# Sheet_MCU_IO.net
KiCad netlist of a schematic drawn in Altium Designer
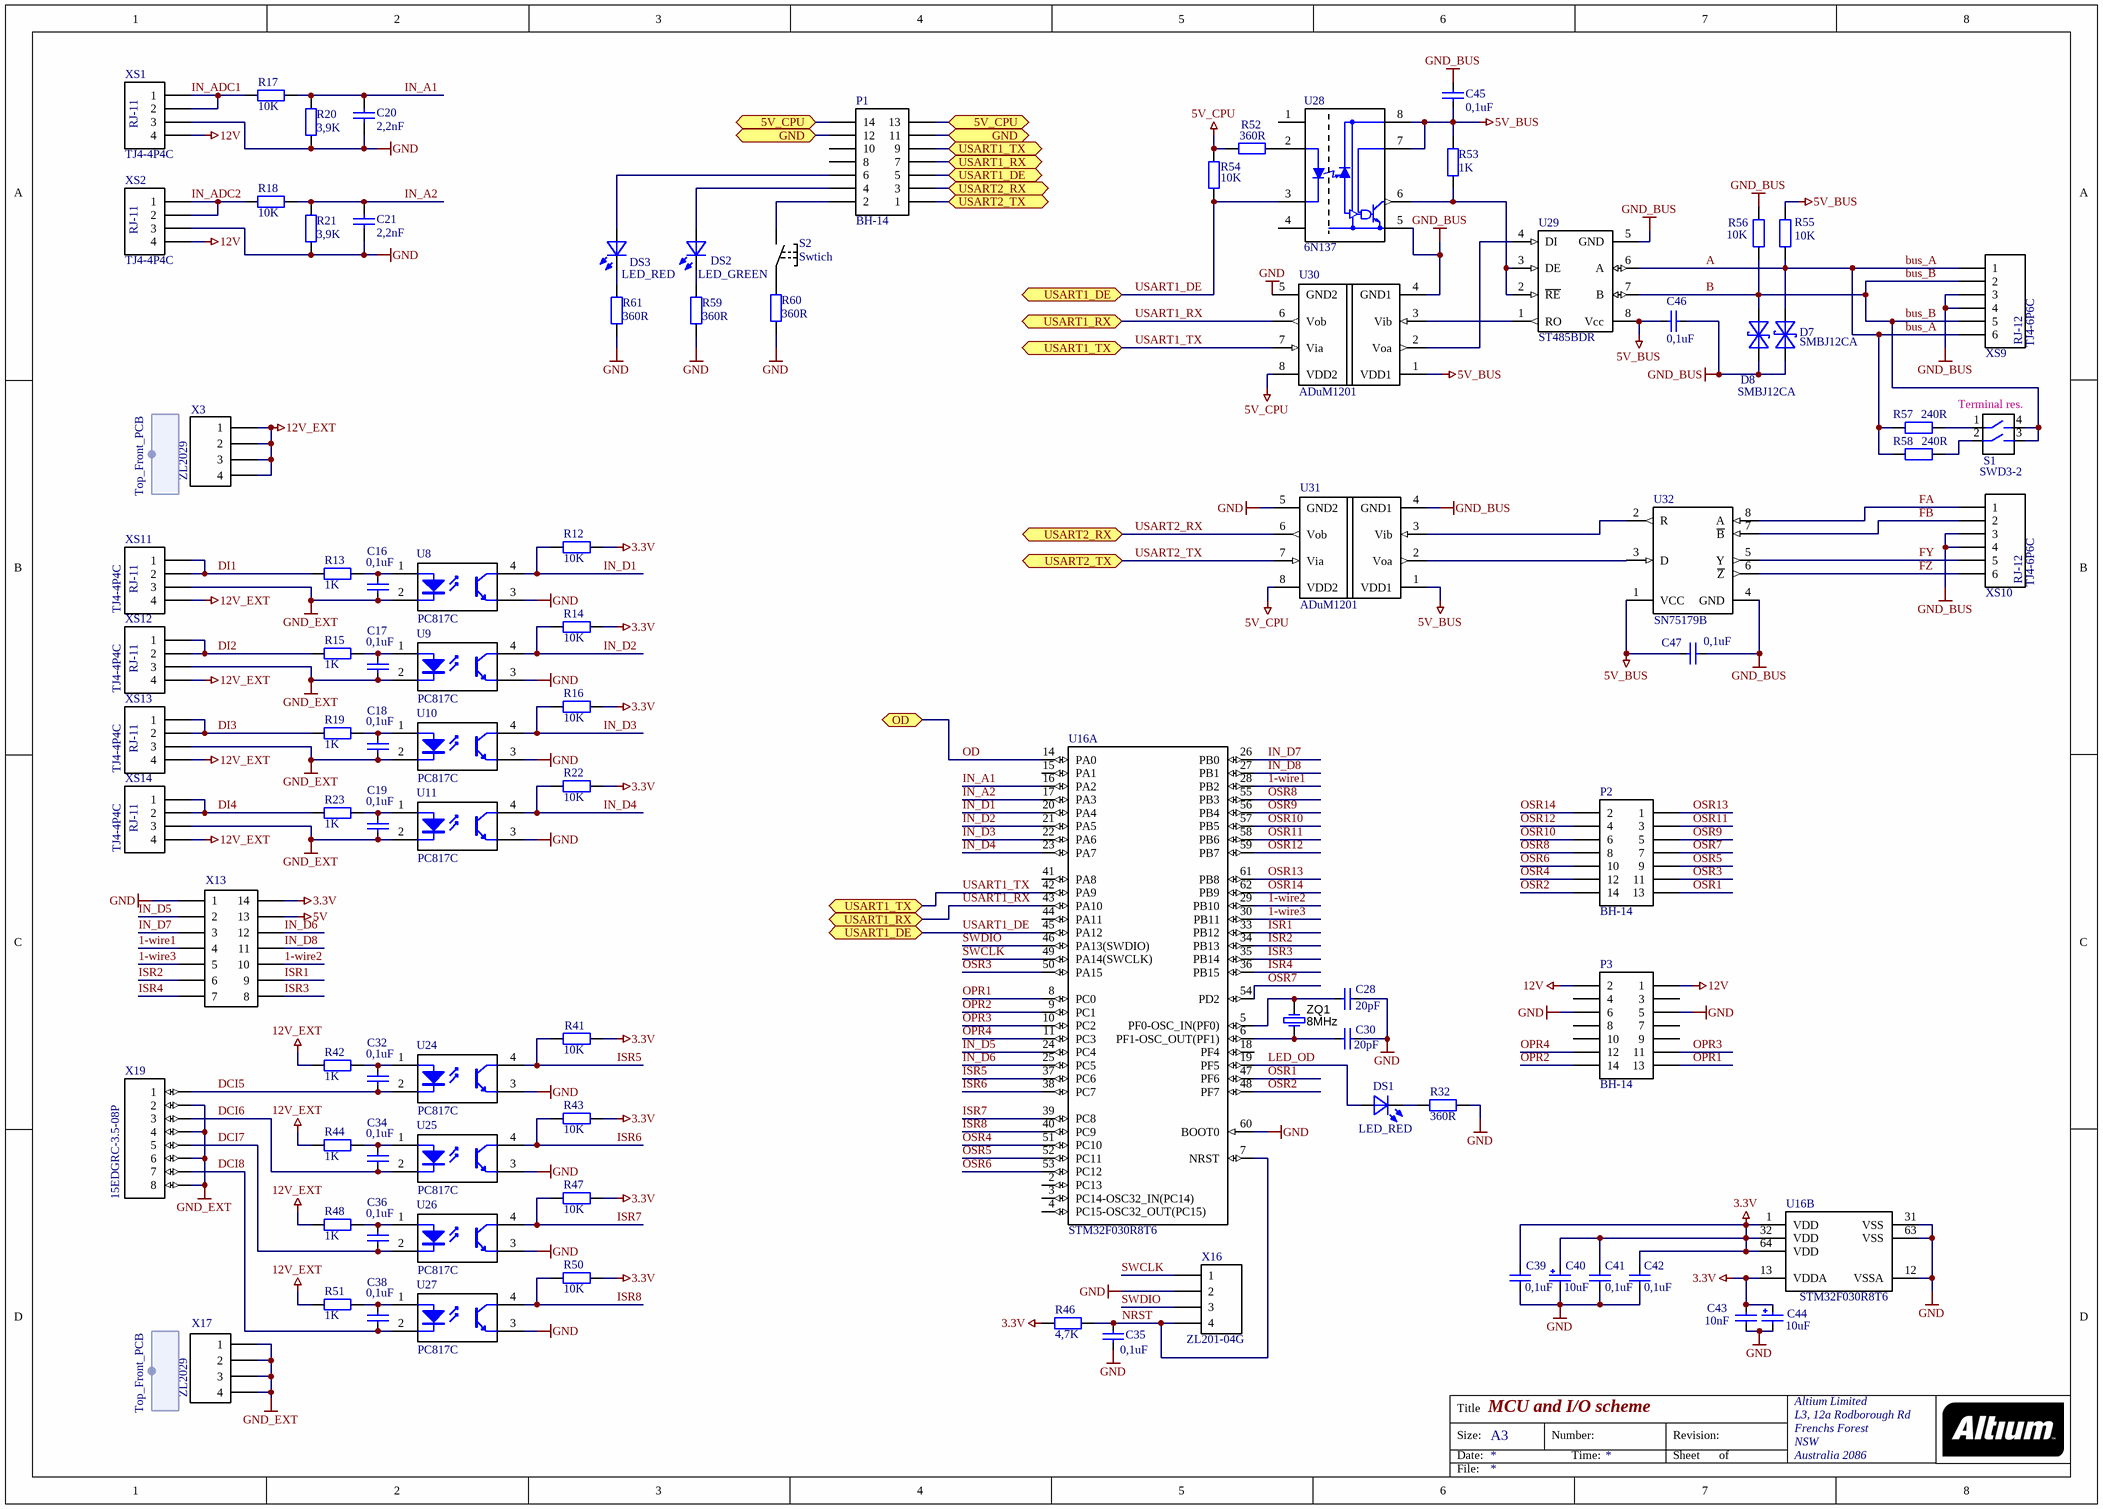
[diagram p0: Sheet_MCU_IO.SchDoc]

(export (version "E")
  (design (tool "Eeschema 10.0.6"))
  (components
    (comp (ref "C16")
      (value "0,1uF")
      (footprint "C_0805")
      (description "Capacitor semi")
      (libsource (lib "Capacitor") (part "Cap_Semi"))
    )
    (comp (ref "C17")
      (value "0,1uF")
      (footprint "C_0805")
      (description "Capacitor semi")
      (libsource (lib "Capacitor") (part "Cap_Semi"))
    )
    (comp (ref "C18")
      (value "0,1uF")
      (footprint "C_0805")
      (description "Capacitor semi")
      (libsource (lib "Capacitor") (part "Cap_Semi"))
    )
    (comp (ref "C19")
      (value "0,1uF")
      (footprint "C_0805")
      (description "Capacitor semi")
      (libsource (lib "Capacitor") (part "Cap_Semi"))
    )
    (comp (ref "C20")
      (value "2,2nF")
      (footprint "C_0805")
      (description "Capacitor Semi")
      (fields (field (name "Comment") "Cap_Semi"))
      (libsource (lib "") (part "Cap_Semi_1"))
    )
    (comp (ref "C21")
      (value "2,2nF")
      (footprint "C_0805")
      (description "Capacitor Semi")
      (fields (field (name "Comment") "Cap_Semi"))
      (libsource (lib "") (part "Cap_Semi_1"))
    )
    (comp (ref "C28")
      (value "20pF")
      (footprint "C_0805")
      (description "Capacitor semi")
      (libsource (lib "Capacitor") (part "Cap_Semi"))
    )
    (comp (ref "C30")
      (value "20pF")
      (footprint "C_0805")
      (description "Capacitor semi")
      (libsource (lib "Capacitor") (part "Cap_Semi"))
    )
    (comp (ref "C32")
      (value "0,1uF")
      (footprint "C_0805")
      (description "Capacitor semi")
      (libsource (lib "Capacitor") (part "Cap_Semi"))
    )
    (comp (ref "C34")
      (value "0,1uF")
      (footprint "C_0805")
      (description "Capacitor semi")
      (libsource (lib "Capacitor") (part "Cap_Semi"))
    )
    (comp (ref "C35")
      (value "0,1uF")
      (footprint "C_0805")
      (description "Capacitor semi")
      (libsource (lib "Capacitor") (part "Cap_Semi"))
    )
    (comp (ref "C36")
      (value "0,1uF")
      (footprint "C_0805")
      (description "Capacitor semi")
      (libsource (lib "Capacitor") (part "Cap_Semi"))
    )
    (comp (ref "C38")
      (value "0,1uF")
      (footprint "C_0805")
      (description "Capacitor semi")
      (libsource (lib "Capacitor") (part "Cap_Semi"))
    )
    (comp (ref "C39")
      (value "0,1uF")
      (footprint "C_0805")
      (description "Capacitor semi")
      (libsource (lib "Capacitor") (part "Cap_Semi"))
    )
    (comp (ref "C40")
      (value "10uF")
      (footprint "5x11")
      (description "Capacitor polar")
      (libsource (lib "Capacitor") (part "Capacitor Polar"))
    )
    (comp (ref "C41")
      (value "0,1uF")
      (footprint "C_0805")
      (description "Capacitor semi")
      (libsource (lib "Capacitor") (part "Cap_Semi"))
    )
    (comp (ref "C42")
      (value "0,1uF")
      (footprint "C_0805")
      (description "Capacitor semi")
      (libsource (lib "Capacitor") (part "Cap_Semi"))
    )
    (comp (ref "C43")
      (value "10nF")
      (footprint "C_0805")
      (description "Capacitor semi")
      (libsource (lib "Capacitor") (part "Cap_Semi"))
    )
    (comp (ref "C44")
      (value "10uF")
      (footprint "5x11")
      (description "Capacitor polar")
      (libsource (lib "Capacitor") (part "Capacitor Polar"))
    )
    (comp (ref "C45")
      (value "0,1uF")
      (footprint "C_0805")
      (description "Capacitor semi")
      (libsource (lib "Capacitor") (part "Cap_Semi"))
    )
    (comp (ref "C46")
      (value "0,1uF")
      (footprint "C_0805")
      (description "Capacitor semi")
      (libsource (lib "Capacitor") (part "Cap_Semi"))
    )
    (comp (ref "C47")
      (value "0,1uF")
      (footprint "C_0805")
      (description "Capacitor semi")
      (libsource (lib "Capacitor") (part "Cap_Semi"))
    )
    (comp (ref "D7")
      (value "SMBJ12CA")
      (footprint "SMB")
      (description "Supressor")
      (libsource (lib "Diode") (part "SMBJ12CA"))
    )
    (comp (ref "D8")
      (value "SMBJ12CA")
      (footprint "SMB")
      (description "Supressor")
      (libsource (lib "Diode") (part "SMBJ12CA"))
    )
    (comp (ref "DS1")
      (value "LED_RED")
      (footprint "LED_RED")
      (description "LED")
      (libsource (lib "LEDs") (part "LED_RED"))
    )
    (comp (ref "DS2")
      (value "LED_GREEN")
      (footprint "LED_GREEN")
      (description "LED")
      (libsource (lib "LEDs") (part "LED_GREEN"))
    )
    (comp (ref "DS3")
      (value "LED_RED")
      (footprint "LED_RED")
      (description "LED")
      (libsource (lib "LEDs") (part "LED_RED"))
    )
    (comp (ref "P1")
      (value "BH-14")
      (footprint "BH-14")
      (description "IDC/BH")
      (fields (field (name "PUBLISHER") "Altium Limited"))
      (libsource (lib "Connect") (part "BH-14"))
    )
    (comp (ref "P2")
      (value "BH-14")
      (footprint "BH-14")
      (description "IDC/BH")
      (fields (field (name "PUBLISHER") "Altium Limited"))
      (libsource (lib "") (part "BH-14_1"))
    )
    (comp (ref "P3")
      (value "BH-14")
      (footprint "BH-14")
      (description "IDC/BH")
      (fields (field (name "PUBLISHER") "Altium Limited"))
      (libsource (lib "") (part "BH-14_1"))
    )
    (comp (ref "R12")
      (value "10K")
      (footprint "R_0805")
      (description "Resistor")
      (libsource (lib "Resistors") (part "Resistor"))
    )
    (comp (ref "R13")
      (value "1K")
      (footprint "R_0805")
      (description "Resistor")
      (libsource (lib "Resistors") (part "Resistor"))
    )
    (comp (ref "R14")
      (value "10K")
      (footprint "R_0805")
      (description "Resistor")
      (libsource (lib "Resistors") (part "Resistor"))
    )
    (comp (ref "R15")
      (value "1K")
      (footprint "R_0805")
      (description "Resistor")
      (libsource (lib "Resistors") (part "Resistor"))
    )
    (comp (ref "R16")
      (value "10K")
      (footprint "R_0805")
      (description "Resistor")
      (libsource (lib "Resistors") (part "Resistor"))
    )
    (comp (ref "R17")
      (value "10K")
      (footprint "R_0805")
      (description "Resistor")
      (libsource (lib "") (part "Resistor_1"))
    )
    (comp (ref "R18")
      (value "10K")
      (footprint "R_0805")
      (description "Resistor")
      (libsource (lib "") (part "Resistor_1"))
    )
    (comp (ref "R19")
      (value "1K")
      (footprint "R_0805")
      (description "Resistor")
      (libsource (lib "Resistors") (part "Resistor"))
    )
    (comp (ref "R20")
      (value "3,9K")
      (footprint "R_0805")
      (description "Resistor")
      (libsource (lib "Resistors") (part "Resistor"))
    )
    (comp (ref "R21")
      (value "3,9K")
      (footprint "R_0805")
      (description "Resistor")
      (libsource (lib "Resistors") (part "Resistor"))
    )
    (comp (ref "R22")
      (value "10K")
      (footprint "R_0805")
      (description "Resistor")
      (libsource (lib "Resistors") (part "Resistor"))
    )
    (comp (ref "R23")
      (value "1K")
      (footprint "R_0805")
      (description "Resistor")
      (libsource (lib "Resistors") (part "Resistor"))
    )
    (comp (ref "R32")
      (value "360R")
      (footprint "R_0805")
      (description "Resistor")
      (libsource (lib "") (part "Resistor_3"))
    )
    (comp (ref "R41")
      (value "10K")
      (footprint "R_0805")
      (description "Resistor")
      (libsource (lib "Resistors") (part "Resistor"))
    )
    (comp (ref "R42")
      (value "1K")
      (footprint "R_0805")
      (description "Resistor")
      (libsource (lib "Resistors") (part "Resistor"))
    )
    (comp (ref "R43")
      (value "10K")
      (footprint "R_0805")
      (description "Resistor")
      (libsource (lib "Resistors") (part "Resistor"))
    )
    (comp (ref "R44")
      (value "1K")
      (footprint "R_0805")
      (description "Resistor")
      (libsource (lib "Resistors") (part "Resistor"))
    )
    (comp (ref "R46")
      (value "4,7K")
      (footprint "R_0805")
      (description "Resistor")
      (libsource (lib "") (part "Resistor_2"))
    )
    (comp (ref "R47")
      (value "10K")
      (footprint "R_0805")
      (description "Resistor")
      (libsource (lib "Resistors") (part "Resistor"))
    )
    (comp (ref "R48")
      (value "1K")
      (footprint "R_0805")
      (description "Resistor")
      (libsource (lib "Resistors") (part "Resistor"))
    )
    (comp (ref "R50")
      (value "10K")
      (footprint "R_0805")
      (description "Resistor")
      (libsource (lib "Resistors") (part "Resistor"))
    )
    (comp (ref "R51")
      (value "1K")
      (footprint "R_0805")
      (description "Resistor")
      (libsource (lib "Resistors") (part "Resistor"))
    )
    (comp (ref "R52")
      (value "360R")
      (footprint "R_0805")
      (description "Resistor")
      (libsource (lib "Resistors") (part "Resistor"))
    )
    (comp (ref "R53")
      (value "1K")
      (footprint "R_0805")
      (description "Resistor 0805")
      (libsource (lib "Resistors") (part "Resistor 0805"))
    )
    (comp (ref "R54")
      (value "10K")
      (footprint "R_0805")
      (description "Resistor")
      (libsource (lib "") (part "Resistor_3"))
    )
    (comp (ref "R55")
      (value "10K")
      (footprint "R_0805")
      (description "Resistor 0805")
      (libsource (lib "Resistors") (part "Resistor 0805"))
    )
    (comp (ref "R56")
      (value "10K")
      (footprint "R_0805")
      (description "Resistor 0805")
      (libsource (lib "Resistors") (part "Resistor 0805"))
    )
    (comp (ref "R57")
      (value "240R")
      (footprint "R_1206")
      (description "Resistor 1206")
      (libsource (lib "Resistors") (part "Resistor 1206"))
    )
    (comp (ref "R58")
      (value "240R")
      (footprint "R_1206")
      (description "Resistor 1206")
      (libsource (lib "Resistors") (part "Resistor 1206"))
    )
    (comp (ref "R59")
      (value "360R")
      (footprint "R_0805")
      (description "Resistor")
      (libsource (lib "") (part "Resistor_1"))
    )
    (comp (ref "R60")
      (value "360R")
      (footprint "R_0805")
      (description "Resistor")
      (libsource (lib "") (part "Resistor_1"))
    )
    (comp (ref "R61")
      (value "360R")
      (footprint "R_0805")
      (description "Resistor")
      (libsource (lib "") (part "Resistor_1"))
    )
    (comp (ref "S1")
      (value "SW DIP-2")
      (footprint "Swich_DIP2")
      (description "DIP Switch_2")
      (fields (field (name "ALTIUM_UNNAMED_1") "SWD3-2"))
      (libsource (lib "Other") (part "SW DIP-2"))
    )
    (comp (ref "S2")
      (value "Swtich")
      (footprint "Swich_TACTA-68N-F_")
      (libsource (lib "Other") (part "Swtich"))
    )
    (comp (ref "U8")
      (value "PC817C")
      (footprint "DIP-4")
      (description "Optocoupler")
      (libsource (lib "Chip_Packaging") (part "PC817"))
    )
    (comp (ref "U9")
      (value "PC817C")
      (footprint "DIP-4")
      (description "Optocoupler")
      (libsource (lib "Chip_Packaging") (part "PC817"))
    )
    (comp (ref "U10")
      (value "PC817C")
      (footprint "DIP-4")
      (description "Optocoupler")
      (libsource (lib "Chip_Packaging") (part "PC817"))
    )
    (comp (ref "U11")
      (value "PC817C")
      (footprint "DIP-4")
      (description "Optocoupler")
      (libsource (lib "Chip_Packaging") (part "PC817"))
    )
    (comp (ref "U16")
      (value "STM32F030R8T6")
      (footprint "LQFP64_L")
      (libsource (lib "Chip_Packaging") (part "STM32F030R8T6"))
    )
    (comp (ref "U24")
      (value "PC817C")
      (footprint "DIP-4")
      (description "Optocoupler")
      (libsource (lib "Chip_Packaging") (part "PC817"))
    )
    (comp (ref "U25")
      (value "PC817C")
      (footprint "DIP-4")
      (description "Optocoupler")
      (libsource (lib "Chip_Packaging") (part "PC817"))
    )
    (comp (ref "U26")
      (value "PC817C")
      (footprint "DIP-4")
      (description "Optocoupler")
      (libsource (lib "Chip_Packaging") (part "PC817"))
    )
    (comp (ref "U27")
      (value "PC817C")
      (footprint "DIP-4")
      (description "Optocoupler")
      (libsource (lib "Chip_Packaging") (part "PC817"))
    )
    (comp (ref "U28")
      (value "6N137")
      (footprint "DIP-8")
      (description "Optocoupler")
      (libsource (lib "Chip_Packaging") (part "6N137"))
    )
    (comp (ref "U29")
      (value "ST485BDR")
      (footprint "SO-8_N")
      (description "RS-485/RS-422 Transceiver")
      (libsource (lib "Chip_Packaging") (part "ST485BDR"))
    )
    (comp (ref "U30")
      (value "ADuM1201")
      (footprint "SO-8_N")
      (description "Dual-Channel Digital Isolators")
      (libsource (lib "Chip_Packaging") (part "ADuM1201"))
    )
    (comp (ref "U31")
      (value "ADuM1201")
      (footprint "SO-8_N")
      (description "Dual-Channel Digital Isolators")
      (libsource (lib "Chip_Packaging") (part "ADuM1201"))
    )
    (comp (ref "U32")
      (value "SN75179B")
      (footprint "SO-8_L")
      (description "RS485/RS422 Differential driver and receiver pair")
      (libsource (lib "Chip_Packaging") (part "SN75179B"))
    )
    (comp (ref "X3")
      (value "ZL2029")
      (footprint "PLS-4-3D")
      (description "Header, 4-Pin")
      (fields (field (name "ALTIUM_UNNAMED_1") "ZL2029") (field (name "PUBLISHER") "Altium Limited"))
      (libsource (lib "Connect") (part "PLS-4"))
    )
    (comp (ref "X13")
      (value "PLS2-14")
      (footprint "PLS2-14")
      (description "Header, 14-Pin")
      (libsource (lib "Connect") (part "PLS2-14"))
    )
    (comp (ref "X16")
      (value "PLS-4")
      (footprint "PLS-4-3D")
      (description "ZL201-04G")
      (fields (field (name "ALTIUM_UNNAMED_1") "ZL201-04G") (field (name "PUBLISHER") "Altium Limited"))
      (libsource (lib "") (part "PLS-4_1"))
    )
    (comp (ref "X17")
      (value "PLS-4")
      (footprint "PLS-4-3D")
      (description "ZL2029")
      (fields (field (name "ALTIUM_UNNAMED_1") "ZL2029") (field (name "PUBLISHER") "Altium Limited"))
      (libsource (lib "Connect") (part "PLS-4"))
    )
    (comp (ref "X19")
      (value "15EDGRC-3.5-08P")
      (footprint "MC_3.5_8")
      (description "Connector 3.5mm")
      (libsource (lib "Connect") (part "MC_3.5_8"))
    )
    (comp (ref "XS1")
      (value "RJ-11")
      (footprint "RJ-11 - TJ4-4P4C")
      (description "TJ4-4P4C")
      (fields (field (name "ALTIUM_UNNAMED_1") "TJ4-4P4C"))
      (libsource (lib "Connect") (part "RJ-11"))
    )
    (comp (ref "XS2")
      (value "RJ-11")
      (footprint "RJ-11 - TJ4-4P4C")
      (description "TJ4-4P4C")
      (fields (field (name "ALTIUM_UNNAMED_1") "TJ4-4P4C"))
      (libsource (lib "Connect") (part "RJ-11"))
    )
    (comp (ref "XS9")
      (value "RJ-12")
      (footprint "RJ-12 - TJ4-6P6C")
      (description "TJ4-6P6C")
      (fields (field (name "ALTIUM_UNNAMED_1") "TJ4-6P6C"))
      (libsource (lib "Connect") (part "RJ-12"))
    )
    (comp (ref "XS10")
      (value "RJ-12")
      (footprint "RJ-12 - TJ4-6P6C")
      (description "TJ4-6P6C")
      (fields (field (name "ALTIUM_UNNAMED_1") "TJ4-6P6C"))
      (libsource (lib "Connect") (part "RJ-12"))
    )
    (comp (ref "XS11")
      (value "RJ-11")
      (footprint "RJ-11 - TJ4-4P4C")
      (description "TJ4-4P4C")
      (fields (field (name "ALTIUM_UNNAMED_1") "TJ4-4P4C"))
      (libsource (lib "Connect") (part "RJ-11"))
    )
    (comp (ref "XS12")
      (value "RJ-11")
      (footprint "RJ-11 - TJ4-4P4C")
      (description "TJ4-4P4C")
      (fields (field (name "ALTIUM_UNNAMED_1") "TJ4-4P4C"))
      (libsource (lib "Connect") (part "RJ-11"))
    )
    (comp (ref "XS13")
      (value "RJ-11")
      (footprint "RJ-11 - TJ4-4P4C")
      (description "TJ4-4P4C")
      (fields (field (name "ALTIUM_UNNAMED_1") "TJ4-4P4C"))
      (libsource (lib "Connect") (part "RJ-11"))
    )
    (comp (ref "XS14")
      (value "RJ-11")
      (footprint "RJ-11 - TJ4-4P4C")
      (description "TJ4-4P4C")
      (fields (field (name "ALTIUM_UNNAMED_1") "TJ4-4P4C"))
      (libsource (lib "Connect") (part "RJ-11"))
    )
    (comp (ref "ZQ1")
      (value "8MHz")
      (footprint "HC49S_3D")
      (description "Crystal Oscillator")
      (fields (field (name "PUBLISHER") "Altium Limited"))
      (libsource (lib "Oscillator") (part "XTAL"))
    )
  )
  (nets
    (net (code "1") (name "/1-wire1") (class "Default")
      (node (ref "U16") (pin "28") (pinfunction "PB2_28") (pintype "bidirectional"))
      (node (ref "X13") (pin "4") (pinfunction "4_4") (pintype "passive"))
    )
    (net (code "2") (name "/1-wire2") (class "Default")
      (node (ref "U16") (pin "29") (pinfunction "PB10_29") (pintype "bidirectional"))
      (node (ref "X13") (pin "10") (pinfunction "10_10") (pintype "passive"))
    )
    (net (code "3") (name "/1-wire3") (class "Default")
      (node (ref "U16") (pin "30") (pinfunction "PB11_30") (pintype "bidirectional"))
      (node (ref "X13") (pin "5") (pinfunction "5_5") (pintype "passive"))
    )
    (net (code "4") (name "/A") (class "Default")
      (node (ref "D7") (pin "2") (pinfunction "C_2") (pintype "passive"))
      (node (ref "R55") (pin "1") (pinfunction "1_1") (pintype "passive"))
      (node (ref "R57") (pin "1") (pinfunction "1_1") (pintype "passive"))
      (node (ref "R58") (pin "1") (pinfunction "1_1") (pintype "passive"))
      (node (ref "U29") (pin "6") (pinfunction "A_6") (pintype "bidirectional"))
      (node (ref "XS9") (pin "1") (pinfunction "1_1") (pintype "passive"))
      (node (ref "XS9") (pin "6") (pinfunction "6_6") (pintype "passive"))
    )
    (net (code "5") (name "/B") (class "Default")
      (node (ref "D8") (pin "1") (pinfunction "A_1") (pintype "passive"))
      (node (ref "R56") (pin "1") (pinfunction "1_1") (pintype "passive"))
      (node (ref "S1") (pin "3") (pinfunction "3_3") (pintype "passive"))
      (node (ref "S1") (pin "4") (pinfunction "4_4") (pintype "passive"))
      (node (ref "U29") (pin "7") (pinfunction "B_7") (pintype "bidirectional"))
      (node (ref "XS9") (pin "2") (pinfunction "2_2") (pintype "passive"))
      (node (ref "XS9") (pin "5") (pinfunction "5_5") (pintype "passive"))
    )
    (net (code "6") (name "/DCI5") (class "Default")
      (node (ref "C32") (pin "2") (pinfunction "2_2") (pintype "passive"))
      (node (ref "U24") (pin "2") (pinfunction "K_2") (pintype "passive"))
      (node (ref "X19") (pin "1") (pinfunction "1_1") (pintype "bidirectional"))
    )
    (net (code "7") (name "/DCI6") (class "Default")
      (node (ref "C34") (pin "2") (pinfunction "2_2") (pintype "passive"))
      (node (ref "U25") (pin "2") (pinfunction "K_2") (pintype "passive"))
      (node (ref "X19") (pin "3") (pinfunction "3_3") (pintype "bidirectional"))
    )
    (net (code "8") (name "/DCI7") (class "Default")
      (node (ref "C36") (pin "2") (pinfunction "2_2") (pintype "passive"))
      (node (ref "U26") (pin "2") (pinfunction "K_2") (pintype "passive"))
      (node (ref "X19") (pin "5") (pinfunction "5_5") (pintype "bidirectional"))
    )
    (net (code "9") (name "/DCI8") (class "Default")
      (node (ref "C38") (pin "2") (pinfunction "2_2") (pintype "passive"))
      (node (ref "U27") (pin "2") (pinfunction "K_2") (pintype "passive"))
      (node (ref "X19") (pin "7") (pinfunction "7_7") (pintype "bidirectional"))
    )
    (net (code "10") (name "/DI1") (class "Default")
      (node (ref "R13") (pin "2") (pinfunction "2_2") (pintype "passive"))
      (node (ref "XS11") (pin "1") (pinfunction "1_1") (pintype "passive"))
      (node (ref "XS11") (pin "2") (pinfunction "2_2") (pintype "passive"))
    )
    (net (code "11") (name "/DI2") (class "Default")
      (node (ref "R15") (pin "2") (pinfunction "2_2") (pintype "passive"))
      (node (ref "XS12") (pin "1") (pinfunction "1_1") (pintype "passive"))
      (node (ref "XS12") (pin "2") (pinfunction "2_2") (pintype "passive"))
    )
    (net (code "12") (name "/DI3") (class "Default")
      (node (ref "R19") (pin "2") (pinfunction "2_2") (pintype "passive"))
      (node (ref "XS13") (pin "1") (pinfunction "1_1") (pintype "passive"))
      (node (ref "XS13") (pin "2") (pinfunction "2_2") (pintype "passive"))
    )
    (net (code "13") (name "/DI4") (class "Default")
      (node (ref "R23") (pin "2") (pinfunction "2_2") (pintype "passive"))
      (node (ref "XS14") (pin "1") (pinfunction "1_1") (pintype "passive"))
      (node (ref "XS14") (pin "2") (pinfunction "2_2") (pintype "passive"))
    )
    (net (code "14") (name "/FA") (class "Default")
      (node (ref "U32") (pin "8") (pinfunction "A_8") (pintype "input"))
      (node (ref "XS10") (pin "1") (pinfunction "1_1") (pintype "passive"))
    )
    (net (code "15") (name "/FY") (class "Default")
      (node (ref "U32") (pin "5") (pinfunction "Y_5") (pintype "output"))
      (node (ref "XS10") (pin "5") (pinfunction "5_5") (pintype "passive"))
    )
    (net (code "16") (name "/F~{B}") (class "Default")
      (node (ref "U32") (pin "7") (pinfunction "~{B}_7") (pintype "input"))
      (node (ref "XS10") (pin "2") (pinfunction "2_2") (pintype "passive"))
    )
    (net (code "17") (name "/F~{Z}") (class "Default")
      (node (ref "U32") (pin "6") (pinfunction "~{Z}_6") (pintype "output"))
      (node (ref "XS10") (pin "6") (pinfunction "6_6") (pintype "passive"))
    )
    (net (code "18") (name "/IN_A1") (class "Default")
      (node (ref "C20") (pin "1") (pinfunction "1_1") (pintype "passive"))
      (node (ref "R17") (pin "1") (pinfunction "1_1") (pintype "passive"))
      (node (ref "R20") (pin "1") (pinfunction "1_1") (pintype "passive"))
      (node (ref "U16") (pin "16") (pinfunction "PA2_16") (pintype "bidirectional"))
    )
    (net (code "19") (name "/IN_A2") (class "Default")
      (node (ref "C21") (pin "1") (pinfunction "1_1") (pintype "passive"))
      (node (ref "R18") (pin "1") (pinfunction "1_1") (pintype "passive"))
      (node (ref "R21") (pin "1") (pinfunction "1_1") (pintype "passive"))
      (node (ref "U16") (pin "17") (pinfunction "PA3_17") (pintype "bidirectional"))
    )
    (net (code "20") (name "/IN_ADC1") (class "Default")
      (node (ref "R17") (pin "2") (pinfunction "2_2") (pintype "passive"))
      (node (ref "XS1") (pin "1") (pinfunction "1_1") (pintype "passive"))
      (node (ref "XS1") (pin "2") (pinfunction "2_2") (pintype "passive"))
    )
    (net (code "21") (name "/IN_ADC2") (class "Default")
      (node (ref "R18") (pin "2") (pinfunction "2_2") (pintype "passive"))
      (node (ref "XS2") (pin "1") (pinfunction "1_1") (pintype "passive"))
      (node (ref "XS2") (pin "2") (pinfunction "2_2") (pintype "passive"))
    )
    (net (code "22") (name "/IN_D1") (class "Default")
      (node (ref "R12") (pin "2") (pinfunction "2_2") (pintype "passive"))
      (node (ref "U16") (pin "20") (pinfunction "PA4_20") (pintype "bidirectional"))
      (node (ref "U8") (pin "4") (pinfunction "C_4") (pintype "passive"))
    )
    (net (code "23") (name "/IN_D2") (class "Default")
      (node (ref "R14") (pin "2") (pinfunction "2_2") (pintype "passive"))
      (node (ref "U16") (pin "21") (pinfunction "PA5_21") (pintype "bidirectional"))
      (node (ref "U9") (pin "4") (pinfunction "C_4") (pintype "passive"))
    )
    (net (code "24") (name "/IN_D3") (class "Default")
      (node (ref "R16") (pin "2") (pinfunction "2_2") (pintype "passive"))
      (node (ref "U10") (pin "4") (pinfunction "C_4") (pintype "passive"))
      (node (ref "U16") (pin "22") (pinfunction "PA6_22") (pintype "bidirectional"))
    )
    (net (code "25") (name "/IN_D4") (class "Default")
      (node (ref "R22") (pin "2") (pinfunction "2_2") (pintype "passive"))
      (node (ref "U11") (pin "4") (pinfunction "C_4") (pintype "passive"))
      (node (ref "U16") (pin "23") (pinfunction "PA7_23") (pintype "bidirectional"))
    )
    (net (code "26") (name "/IN_D5") (class "Default")
      (node (ref "U16") (pin "24") (pinfunction "PC4_24") (pintype "bidirectional"))
      (node (ref "X13") (pin "2") (pinfunction "2_2") (pintype "passive"))
    )
    (net (code "27") (name "/IN_D6") (class "Default")
      (node (ref "U16") (pin "25") (pinfunction "PC5_25") (pintype "bidirectional"))
      (node (ref "X13") (pin "12") (pinfunction "12_12") (pintype "passive"))
    )
    (net (code "28") (name "/IN_D7") (class "Default")
      (node (ref "U16") (pin "26") (pinfunction "PB0_26") (pintype "bidirectional"))
      (node (ref "X13") (pin "3") (pinfunction "3_3") (pintype "passive"))
    )
    (net (code "29") (name "/IN_D8") (class "Default")
      (node (ref "U16") (pin "27") (pinfunction "PB1_27") (pintype "bidirectional"))
      (node (ref "X13") (pin "11") (pinfunction "11_11") (pintype "passive"))
    )
    (net (code "30") (name "/ISR1") (class "Default")
      (node (ref "U16") (pin "33") (pinfunction "PB12_33") (pintype "bidirectional"))
      (node (ref "X13") (pin "9") (pinfunction "9_9") (pintype "passive"))
    )
    (net (code "31") (name "/ISR2") (class "Default")
      (node (ref "U16") (pin "34") (pinfunction "PB13_34") (pintype "bidirectional"))
      (node (ref "X13") (pin "6") (pinfunction "6_6") (pintype "passive"))
    )
    (net (code "32") (name "/ISR3") (class "Default")
      (node (ref "U16") (pin "35") (pinfunction "PB14_35") (pintype "bidirectional"))
      (node (ref "X13") (pin "8") (pinfunction "8_8") (pintype "passive"))
    )
    (net (code "33") (name "/ISR4") (class "Default")
      (node (ref "U16") (pin "36") (pinfunction "PB15_36") (pintype "bidirectional"))
      (node (ref "X13") (pin "7") (pinfunction "7_7") (pintype "passive"))
    )
    (net (code "34") (name "/ISR5") (class "Default")
      (node (ref "R41") (pin "2") (pinfunction "2_2") (pintype "passive"))
      (node (ref "U16") (pin "37") (pinfunction "PC6_37") (pintype "bidirectional"))
      (node (ref "U24") (pin "4") (pinfunction "C_4") (pintype "passive"))
    )
    (net (code "35") (name "/ISR6") (class "Default")
      (node (ref "R43") (pin "2") (pinfunction "2_2") (pintype "passive"))
      (node (ref "U16") (pin "38") (pinfunction "PC7_38") (pintype "bidirectional"))
      (node (ref "U25") (pin "4") (pinfunction "C_4") (pintype "passive"))
    )
    (net (code "36") (name "/ISR7") (class "Default")
      (node (ref "R47") (pin "2") (pinfunction "2_2") (pintype "passive"))
      (node (ref "U16") (pin "39") (pinfunction "PC8_39") (pintype "bidirectional"))
      (node (ref "U26") (pin "4") (pinfunction "C_4") (pintype "passive"))
    )
    (net (code "37") (name "/ISR8") (class "Default")
      (node (ref "R50") (pin "2") (pinfunction "2_2") (pintype "passive"))
      (node (ref "U16") (pin "40") (pinfunction "PC9_40") (pintype "bidirectional"))
      (node (ref "U27") (pin "4") (pinfunction "C_4") (pintype "passive"))
    )
    (net (code "38") (name "/LED_OD") (class "Default")
      (node (ref "DS1") (pin "1") (pinfunction "A_1") (pintype "passive"))
      (node (ref "U16") (pin "19") (pinfunction "PF5_19") (pintype "bidirectional"))
    )
    (net (code "39") (name "/NRST") (class "Default")
      (node (ref "C35") (pin "1") (pinfunction "1_1") (pintype "passive"))
      (node (ref "R46") (pin "2") (pinfunction "2_2") (pintype "passive"))
      (node (ref "U16") (pin "7") (pinfunction "NRST_7") (pintype "bidirectional"))
      (node (ref "X16") (pin "4") (pinfunction "4_4") (pintype "passive"))
    )
    (net (code "40") (name "/OD") (class "Default")
      (node (ref "U16") (pin "14") (pinfunction "PA0_14") (pintype "bidirectional"))
    )
    (net (code "41") (name "/OPR1") (class "Default")
      (node (ref "P3") (pin "13") (pinfunction "13_13") (pintype "passive"))
      (node (ref "U16") (pin "8") (pinfunction "PC0_8") (pintype "bidirectional"))
    )
    (net (code "42") (name "/OPR2") (class "Default")
      (node (ref "P3") (pin "14") (pinfunction "14_14") (pintype "passive"))
      (node (ref "U16") (pin "9") (pinfunction "PC1_9") (pintype "bidirectional"))
    )
    (net (code "43") (name "/OPR3") (class "Default")
      (node (ref "P3") (pin "11") (pinfunction "11_11") (pintype "passive"))
      (node (ref "U16") (pin "10") (pinfunction "PC2_10") (pintype "bidirectional"))
    )
    (net (code "44") (name "/OPR4") (class "Default")
      (node (ref "P3") (pin "12") (pinfunction "12_12") (pintype "passive"))
      (node (ref "U16") (pin "11") (pinfunction "PC3_11") (pintype "bidirectional"))
    )
    (net (code "45") (name "/OSR1") (class "Default")
      (node (ref "P2") (pin "13") (pinfunction "13_13") (pintype "passive"))
      (node (ref "U16") (pin "47") (pinfunction "PF6_47") (pintype "bidirectional"))
    )
    (net (code "46") (name "/OSR2") (class "Default")
      (node (ref "P2") (pin "14") (pinfunction "14_14") (pintype "passive"))
      (node (ref "U16") (pin "48") (pinfunction "PF7_48") (pintype "bidirectional"))
    )
    (net (code "47") (name "/OSR3") (class "Default")
      (node (ref "P2") (pin "11") (pinfunction "11_11") (pintype "passive"))
      (node (ref "U16") (pin "50") (pinfunction "PA15_50") (pintype "bidirectional"))
    )
    (net (code "48") (name "/OSR4") (class "Default")
      (node (ref "P2") (pin "12") (pinfunction "12_12") (pintype "passive"))
      (node (ref "U16") (pin "51") (pinfunction "PC10_51") (pintype "bidirectional"))
    )
    (net (code "49") (name "/OSR5") (class "Default")
      (node (ref "P2") (pin "9") (pinfunction "9_9") (pintype "passive"))
      (node (ref "U16") (pin "52") (pinfunction "PC11_52") (pintype "bidirectional"))
    )
    (net (code "50") (name "/OSR6") (class "Default")
      (node (ref "P2") (pin "10") (pinfunction "10_10") (pintype "passive"))
      (node (ref "U16") (pin "53") (pinfunction "PC12_53") (pintype "bidirectional"))
    )
    (net (code "51") (name "/OSR7") (class "Default")
      (node (ref "P2") (pin "7") (pinfunction "7_7") (pintype "passive"))
      (node (ref "U16") (pin "54") (pinfunction "PD2_54") (pintype "bidirectional"))
    )
    (net (code "52") (name "/OSR8") (class "Default")
      (node (ref "P2") (pin "8") (pinfunction "8_8") (pintype "passive"))
      (node (ref "U16") (pin "55") (pinfunction "PB3_55") (pintype "bidirectional"))
    )
    (net (code "53") (name "/OSR9") (class "Default")
      (node (ref "P2") (pin "5") (pinfunction "5_5") (pintype "passive"))
      (node (ref "U16") (pin "56") (pinfunction "PB4_56") (pintype "bidirectional"))
    )
    (net (code "54") (name "/OSR10") (class "Default")
      (node (ref "P2") (pin "6") (pinfunction "6_6") (pintype "passive"))
      (node (ref "U16") (pin "57") (pinfunction "PB5_57") (pintype "bidirectional"))
    )
    (net (code "55") (name "/OSR11") (class "Default")
      (node (ref "P2") (pin "3") (pinfunction "3_3") (pintype "passive"))
      (node (ref "U16") (pin "58") (pinfunction "PB6_58") (pintype "bidirectional"))
    )
    (net (code "56") (name "/OSR12") (class "Default")
      (node (ref "P2") (pin "4") (pinfunction "4_4") (pintype "passive"))
      (node (ref "U16") (pin "59") (pinfunction "PB7_59") (pintype "bidirectional"))
    )
    (net (code "57") (name "/OSR13") (class "Default")
      (node (ref "P2") (pin "1") (pinfunction "1_1") (pintype "passive"))
      (node (ref "U16") (pin "61") (pinfunction "PB8_61") (pintype "bidirectional"))
    )
    (net (code "58") (name "/OSR14") (class "Default")
      (node (ref "P2") (pin "2") (pinfunction "2_2") (pintype "passive"))
      (node (ref "U16") (pin "62") (pinfunction "PB9_62") (pintype "bidirectional"))
    )
    (net (code "59") (name "/SWCLK") (class "Default")
      (node (ref "U16") (pin "49") (pinfunction "PA14(SWCLK)_49") (pintype "bidirectional"))
      (node (ref "X16") (pin "1") (pinfunction "1_1") (pintype "passive"))
    )
    (net (code "60") (name "/SWDIO") (class "Default")
      (node (ref "U16") (pin "46") (pinfunction "PA13(SWDIO)_46") (pintype "bidirectional"))
      (node (ref "X16") (pin "3") (pinfunction "3_3") (pintype "passive"))
    )
    (net (code "61") (name "/USART1_DE") (class "Default")
      (node (ref "P1") (pin "5") (pinfunction "5_5") (pintype "passive"))
      (node (ref "R54") (pin "1") (pinfunction "1_1") (pintype "passive"))
      (node (ref "U16") (pin "45") (pinfunction "PA12_45") (pintype "bidirectional"))
      (node (ref "U28") (pin "3") (pinfunction "C_3") (pintype "passive"))
    )
    (net (code "62") (name "/USART1_RX") (class "Default")
      (node (ref "P1") (pin "7") (pinfunction "7_7") (pintype "passive"))
      (node (ref "U16") (pin "43") (pinfunction "PA10_43") (pintype "bidirectional"))
      (node (ref "U30") (pin "6") (pinfunction "Vob_6") (pintype "output"))
    )
    (net (code "63") (name "/USART1_TX") (class "Default")
      (node (ref "P1") (pin "9") (pinfunction "9_9") (pintype "passive"))
      (node (ref "U16") (pin "42") (pinfunction "PA9_42") (pintype "bidirectional"))
      (node (ref "U30") (pin "7") (pinfunction "Via_7") (pintype "input"))
    )
    (net (code "64") (name "/USART2_RX") (class "Default")
      (node (ref "P1") (pin "3") (pinfunction "3_3") (pintype "passive"))
      (node (ref "U31") (pin "6") (pinfunction "Vob_6") (pintype "output"))
    )
    (net (code "65") (name "/USART2_TX") (class "Default")
      (node (ref "P1") (pin "1") (pinfunction "1_1") (pintype "passive"))
      (node (ref "U31") (pin "7") (pinfunction "Via_7") (pintype "input"))
    )
    (net (code "66") (name "3.3V") (class "Default")
      (node (ref "C39") (pin "1") (pinfunction "1_1") (pintype "passive"))
      (node (ref "C40") (pin "1") (pinfunction "1_1") (pintype "passive"))
      (node (ref "C41") (pin "1") (pinfunction "1_1") (pintype "passive"))
      (node (ref "C42") (pin "1") (pinfunction "1_1") (pintype "passive"))
      (node (ref "C43") (pin "1") (pinfunction "1_1") (pintype "passive"))
      (node (ref "C44") (pin "1") (pinfunction "1_1") (pintype "passive"))
      (node (ref "R12") (pin "1") (pinfunction "1_1") (pintype "passive"))
      (node (ref "R14") (pin "1") (pinfunction "1_1") (pintype "passive"))
      (node (ref "R16") (pin "1") (pinfunction "1_1") (pintype "passive"))
      (node (ref "R22") (pin "1") (pinfunction "1_1") (pintype "passive"))
      (node (ref "R41") (pin "1") (pinfunction "1_1") (pintype "passive"))
      (node (ref "R43") (pin "1") (pinfunction "1_1") (pintype "passive"))
      (node (ref "R46") (pin "1") (pinfunction "1_1") (pintype "passive"))
      (node (ref "R47") (pin "1") (pinfunction "1_1") (pintype "passive"))
      (node (ref "R50") (pin "1") (pinfunction "1_1") (pintype "passive"))
      (node (ref "U16") (pin "1") (pinfunction "VDD_1") (pintype "power_in"))
      (node (ref "U16") (pin "13") (pinfunction "VDDA_13") (pintype "power_in"))
      (node (ref "U16") (pin "32") (pinfunction "VDD_32") (pintype "power_in"))
      (node (ref "U16") (pin "64") (pinfunction "VDD_64") (pintype "power_in"))
      (node (ref "X13") (pin "14") (pinfunction "14_14") (pintype "passive"))
    )
    (net (code "67") (name "5V") (class "Default")
      (node (ref "X13") (pin "13") (pinfunction "13_13") (pintype "passive"))
    )
    (net (code "68") (name "5V_BUS") (class "Default")
      (node (ref "C45") (pin "1") (pinfunction "1_1") (pintype "passive"))
      (node (ref "C46") (pin "2") (pinfunction "2_2") (pintype "passive"))
      (node (ref "C47") (pin "2") (pinfunction "2_2") (pintype "passive"))
      (node (ref "R53") (pin "2") (pinfunction "2_2") (pintype "passive"))
      (node (ref "R55") (pin "2") (pinfunction "2_2") (pintype "passive"))
      (node (ref "U28") (pin "7") (pinfunction "Ve_7") (pintype "passive"))
      (node (ref "U28") (pin "8") (pinfunction "Vcc_8") (pintype "power_in"))
      (node (ref "U29") (pin "8") (pinfunction "Vcc_8") (pintype "power_in"))
      (node (ref "U30") (pin "1") (pinfunction "VDD1_1") (pintype "power_in"))
      (node (ref "U31") (pin "1") (pinfunction "VDD1_1") (pintype "power_in"))
      (node (ref "U32") (pin "1") (pinfunction "VCC_1") (pintype "power_in"))
    )
    (net (code "69") (name "5V_CPU") (class "Default")
      (node (ref "P1") (pin "13") (pinfunction "13_13") (pintype "passive"))
      (node (ref "P1") (pin "14") (pinfunction "14_14") (pintype "passive"))
      (node (ref "R52") (pin "2") (pinfunction "2_2") (pintype "passive"))
      (node (ref "R54") (pin "2") (pinfunction "2_2") (pintype "passive"))
      (node (ref "U30") (pin "8") (pinfunction "VDD2_8") (pintype "power_in"))
      (node (ref "U31") (pin "8") (pinfunction "VDD2_8") (pintype "power_in"))
    )
    (net (code "70") (name "12V") (class "Default")
      (node (ref "P3") (pin "1") (pinfunction "1_1") (pintype "passive"))
      (node (ref "P3") (pin "2") (pinfunction "2_2") (pintype "passive"))
      (node (ref "XS1") (pin "4") (pinfunction "4_4") (pintype "passive"))
      (node (ref "XS2") (pin "4") (pinfunction "4_4") (pintype "passive"))
    )
    (net (code "71") (name "12V_EXT") (class "Default")
      (node (ref "R42") (pin "2") (pinfunction "2_2") (pintype "passive"))
      (node (ref "R44") (pin "2") (pinfunction "2_2") (pintype "passive"))
      (node (ref "R48") (pin "2") (pinfunction "2_2") (pintype "passive"))
      (node (ref "R51") (pin "2") (pinfunction "2_2") (pintype "passive"))
      (node (ref "X3") (pin "1") (pinfunction "1_1") (pintype "passive"))
      (node (ref "X3") (pin "2") (pinfunction "2_2") (pintype "passive"))
      (node (ref "X3") (pin "3") (pinfunction "3_3") (pintype "passive"))
      (node (ref "X3") (pin "4") (pinfunction "4_4") (pintype "passive"))
      (node (ref "XS11") (pin "4") (pinfunction "4_4") (pintype "passive"))
      (node (ref "XS12") (pin "4") (pinfunction "4_4") (pintype "passive"))
      (node (ref "XS13") (pin "4") (pinfunction "4_4") (pintype "passive"))
      (node (ref "XS14") (pin "4") (pinfunction "4_4") (pintype "passive"))
    )
    (net (code "72") (name "GND") (class "Default")
      (node (ref "C20") (pin "2") (pinfunction "2_2") (pintype "passive"))
      (node (ref "C21") (pin "2") (pinfunction "2_2") (pintype "passive"))
      (node (ref "C28") (pin "1") (pinfunction "1_1") (pintype "passive"))
      (node (ref "C30") (pin "1") (pinfunction "1_1") (pintype "passive"))
      (node (ref "C35") (pin "2") (pinfunction "2_2") (pintype "passive"))
      (node (ref "C39") (pin "2") (pinfunction "2_2") (pintype "passive"))
      (node (ref "C40") (pin "2") (pinfunction "2_2") (pintype "passive"))
      (node (ref "C41") (pin "2") (pinfunction "2_2") (pintype "passive"))
      (node (ref "C42") (pin "2") (pinfunction "2_2") (pintype "passive"))
      (node (ref "C43") (pin "2") (pinfunction "2_2") (pintype "passive"))
      (node (ref "C44") (pin "2") (pinfunction "2_2") (pintype "passive"))
      (node (ref "P1") (pin "11") (pinfunction "11_11") (pintype "passive"))
      (node (ref "P1") (pin "12") (pinfunction "12_12") (pintype "passive"))
      (node (ref "P3") (pin "5") (pinfunction "5_5") (pintype "passive"))
      (node (ref "P3") (pin "6") (pinfunction "6_6") (pintype "passive"))
      (node (ref "R20") (pin "2") (pinfunction "2_2") (pintype "passive"))
      (node (ref "R21") (pin "2") (pinfunction "2_2") (pintype "passive"))
      (node (ref "R32") (pin "2") (pinfunction "2_2") (pintype "passive"))
      (node (ref "R59") (pin "2") (pinfunction "2_2") (pintype "passive"))
      (node (ref "R60") (pin "2") (pinfunction "2_2") (pintype "passive"))
      (node (ref "R61") (pin "2") (pinfunction "2_2") (pintype "passive"))
      (node (ref "U10") (pin "3") (pinfunction "E_3") (pintype "passive"))
      (node (ref "U11") (pin "3") (pinfunction "E_3") (pintype "passive"))
      (node (ref "U16") (pin "12") (pinfunction "VSSA_12") (pintype "power_in"))
      (node (ref "U16") (pin "31") (pinfunction "VSS_31") (pintype "power_in"))
      (node (ref "U16") (pin "60") (pinfunction "BOOT0_60") (pintype "input"))
      (node (ref "U16") (pin "63") (pinfunction "VSS_63") (pintype "power_in"))
      (node (ref "U24") (pin "3") (pinfunction "E_3") (pintype "passive"))
      (node (ref "U25") (pin "3") (pinfunction "E_3") (pintype "passive"))
      (node (ref "U26") (pin "3") (pinfunction "E_3") (pintype "passive"))
      (node (ref "U27") (pin "3") (pinfunction "E_3") (pintype "passive"))
      (node (ref "U30") (pin "5") (pinfunction "GND2_5") (pintype "power_in"))
      (node (ref "U31") (pin "5") (pinfunction "GND2_5") (pintype "power_in"))
      (node (ref "U8") (pin "3") (pinfunction "E_3") (pintype "passive"))
      (node (ref "U9") (pin "3") (pinfunction "E_3") (pintype "passive"))
      (node (ref "X13") (pin "1") (pinfunction "1_1") (pintype "passive"))
      (node (ref "X16") (pin "2") (pinfunction "2_2") (pintype "passive"))
      (node (ref "XS1") (pin "3") (pinfunction "3_3") (pintype "passive"))
      (node (ref "XS2") (pin "3") (pinfunction "3_3") (pintype "passive"))
    )
    (net (code "73") (name "GND_BUS") (class "Default")
      (node (ref "C45") (pin "2") (pinfunction "2_2") (pintype "passive"))
      (node (ref "C46") (pin "1") (pinfunction "1_1") (pintype "passive"))
      (node (ref "C47") (pin "1") (pinfunction "1_1") (pintype "passive"))
      (node (ref "D7") (pin "1") (pinfunction "A_1") (pintype "passive"))
      (node (ref "D8") (pin "2") (pinfunction "C_2") (pintype "passive"))
      (node (ref "R56") (pin "2") (pinfunction "2_2") (pintype "passive"))
      (node (ref "U28") (pin "5") (pinfunction "GND_5") (pintype "power_in"))
      (node (ref "U29") (pin "5") (pinfunction "GND_5") (pintype "power_in"))
      (node (ref "U30") (pin "4") (pinfunction "GND1_4") (pintype "power_in"))
      (node (ref "U31") (pin "4") (pinfunction "GND1_4") (pintype "power_in"))
      (node (ref "U32") (pin "4") (pinfunction "GND_4") (pintype "power_in"))
      (node (ref "XS10") (pin "3") (pinfunction "3_3") (pintype "passive"))
      (node (ref "XS10") (pin "4") (pinfunction "4_4") (pintype "passive"))
      (node (ref "XS9") (pin "3") (pinfunction "3_3") (pintype "passive"))
      (node (ref "XS9") (pin "4") (pinfunction "4_4") (pintype "passive"))
    )
    (net (code "74") (name "GND_EXT") (class "Default")
      (node (ref "C16") (pin "2") (pinfunction "2_2") (pintype "passive"))
      (node (ref "C17") (pin "2") (pinfunction "2_2") (pintype "passive"))
      (node (ref "C18") (pin "2") (pinfunction "2_2") (pintype "passive"))
      (node (ref "C19") (pin "2") (pinfunction "2_2") (pintype "passive"))
      (node (ref "U10") (pin "2") (pinfunction "K_2") (pintype "passive"))
      (node (ref "U11") (pin "2") (pinfunction "K_2") (pintype "passive"))
      (node (ref "U8") (pin "2") (pinfunction "K_2") (pintype "passive"))
      (node (ref "U9") (pin "2") (pinfunction "K_2") (pintype "passive"))
      (node (ref "X17") (pin "1") (pinfunction "1_1") (pintype "passive"))
      (node (ref "X17") (pin "2") (pinfunction "2_2") (pintype "passive"))
      (node (ref "X17") (pin "3") (pinfunction "3_3") (pintype "passive"))
      (node (ref "X17") (pin "4") (pinfunction "4_4") (pintype "passive"))
      (node (ref "X19") (pin "2") (pinfunction "2_2") (pintype "bidirectional"))
      (node (ref "X19") (pin "4") (pinfunction "4_4") (pintype "bidirectional"))
      (node (ref "X19") (pin "6") (pinfunction "6_6") (pintype "bidirectional"))
      (node (ref "X19") (pin "8") (pinfunction "8_8") (pintype "bidirectional"))
      (node (ref "XS11") (pin "3") (pinfunction "3_3") (pintype "passive"))
      (node (ref "XS12") (pin "3") (pinfunction "3_3") (pintype "passive"))
      (node (ref "XS13") (pin "3") (pinfunction "3_3") (pintype "passive"))
      (node (ref "XS14") (pin "3") (pinfunction "3_3") (pintype "passive"))
    )
    (net (code "75") (name "Net-(DS1-C)") (class "Default")
      (node (ref "DS1") (pin "2") (pinfunction "C_2") (pintype "passive"))
      (node (ref "R32") (pin "1") (pinfunction "1_1") (pintype "passive"))
    )
    (net (code "76") (name "Net-(DS2-A)") (class "Default")
      (node (ref "DS2") (pin "1") (pinfunction "A_1") (pintype "passive"))
      (node (ref "P1") (pin "4") (pinfunction "4_4") (pintype "passive"))
    )
    (net (code "77") (name "Net-(DS2-C)") (class "Default")
      (node (ref "DS2") (pin "2") (pinfunction "C_2") (pintype "passive"))
      (node (ref "R59") (pin "1") (pinfunction "1_1") (pintype "passive"))
    )
    (net (code "78") (name "Net-(DS3-A)") (class "Default")
      (node (ref "DS3") (pin "1") (pinfunction "A_1") (pintype "passive"))
      (node (ref "P1") (pin "6") (pinfunction "6_6") (pintype "passive"))
    )
    (net (code "79") (name "Net-(DS3-C)") (class "Default")
      (node (ref "DS3") (pin "2") (pinfunction "C_2") (pintype "passive"))
      (node (ref "R61") (pin "1") (pinfunction "1_1") (pintype "passive"))
    )
    (net (code "80") (name "Net-(R57-Pad2)") (class "Default")
      (node (ref "R57") (pin "2") (pinfunction "2_2") (pintype "passive"))
      (node (ref "S1") (pin "1") (pinfunction "1_1") (pintype "passive"))
    )
    (net (code "81") (name "Net-(R58-Pad2)") (class "Default")
      (node (ref "R58") (pin "2") (pinfunction "2_2") (pintype "passive"))
      (node (ref "S1") (pin "2") (pinfunction "2_2") (pintype "passive"))
    )
    (net (code "82") (name "Net-(S2-COMMON)") (class "Default")
      (node (ref "R60") (pin "1") (pinfunction "1_1") (pintype "passive"))
      (node (ref "S2") (pin "1") (pinfunction "COMMON_1") (pintype "passive"))
    )
    (net (code "83") (name "Net-(S2-NO)") (class "Default")
      (node (ref "P1") (pin "2") (pinfunction "2_2") (pintype "passive"))
      (node (ref "S2") (pin "2") (pinfunction "NO_2") (pintype "passive"))
    )
    (net (code "84") (name "Net-(U8-A)") (class "Default")
      (node (ref "C16") (pin "1") (pinfunction "1_1") (pintype "passive"))
      (node (ref "R13") (pin "1") (pinfunction "1_1") (pintype "passive"))
      (node (ref "U8") (pin "1") (pinfunction "A_1") (pintype "passive"))
    )
    (net (code "85") (name "Net-(U9-A)") (class "Default")
      (node (ref "C17") (pin "1") (pinfunction "1_1") (pintype "passive"))
      (node (ref "R15") (pin "1") (pinfunction "1_1") (pintype "passive"))
      (node (ref "U9") (pin "1") (pinfunction "A_1") (pintype "passive"))
    )
    (net (code "86") (name "Net-(U10-A)") (class "Default")
      (node (ref "C18") (pin "1") (pinfunction "1_1") (pintype "passive"))
      (node (ref "R19") (pin "1") (pinfunction "1_1") (pintype "passive"))
      (node (ref "U10") (pin "1") (pinfunction "A_1") (pintype "passive"))
    )
    (net (code "87") (name "Net-(U11-A)") (class "Default")
      (node (ref "C19") (pin "1") (pinfunction "1_1") (pintype "passive"))
      (node (ref "R23") (pin "1") (pinfunction "1_1") (pintype "passive"))
      (node (ref "U11") (pin "1") (pinfunction "A_1") (pintype "passive"))
    )
    (net (code "88") (name "Net-(U16A-PF0-OSC_IN(PF0))") (class "Default")
      (node (ref "C28") (pin "2") (pinfunction "2_2") (pintype "passive"))
      (node (ref "U16") (pin "5") (pinfunction "PF0-OSC_IN(PF0)_5") (pintype "bidirectional"))
      (node (ref "ZQ1") (pin "2") (pinfunction "OSC2_2") (pintype "passive"))
    )
    (net (code "89") (name "Net-(U16A-PF1-OSC_OUT(PF1))") (class "Default")
      (node (ref "C30") (pin "2") (pinfunction "2_2") (pintype "passive"))
      (node (ref "U16") (pin "6") (pinfunction "PF1-OSC_OUT(PF1)_6") (pintype "bidirectional"))
      (node (ref "ZQ1") (pin "1") (pinfunction "OSC1_1") (pintype "passive"))
    )
    (net (code "90") (name "Net-(U24-A)") (class "Default")
      (node (ref "C32") (pin "1") (pinfunction "1_1") (pintype "passive"))
      (node (ref "R42") (pin "1") (pinfunction "1_1") (pintype "passive"))
      (node (ref "U24") (pin "1") (pinfunction "A_1") (pintype "passive"))
    )
    (net (code "91") (name "Net-(U25-A)") (class "Default")
      (node (ref "C34") (pin "1") (pinfunction "1_1") (pintype "passive"))
      (node (ref "R44") (pin "1") (pinfunction "1_1") (pintype "passive"))
      (node (ref "U25") (pin "1") (pinfunction "A_1") (pintype "passive"))
    )
    (net (code "92") (name "Net-(U26-A)") (class "Default")
      (node (ref "C36") (pin "1") (pinfunction "1_1") (pintype "passive"))
      (node (ref "R48") (pin "1") (pinfunction "1_1") (pintype "passive"))
      (node (ref "U26") (pin "1") (pinfunction "A_1") (pintype "passive"))
    )
    (net (code "93") (name "Net-(U27-A)") (class "Default")
      (node (ref "C38") (pin "1") (pinfunction "1_1") (pintype "passive"))
      (node (ref "R51") (pin "1") (pinfunction "1_1") (pintype "passive"))
      (node (ref "U27") (pin "1") (pinfunction "A_1") (pintype "passive"))
    )
    (net (code "94") (name "Net-(U28-A)") (class "Default")
      (node (ref "R52") (pin "1") (pinfunction "1_1") (pintype "passive"))
      (node (ref "U28") (pin "2") (pinfunction "A_2") (pintype "passive"))
    )
    (net (code "95") (name "Net-(U28-Vo)") (class "Default")
      (node (ref "R53") (pin "1") (pinfunction "1_1") (pintype "passive"))
      (node (ref "U28") (pin "6") (pinfunction "Vo_6") (pintype "output"))
      (node (ref "U29") (pin "2") (pinfunction "~{RE}_2") (pintype "input"))
      (node (ref "U29") (pin "3") (pinfunction "DE_3") (pintype "input"))
    )
    (net (code "96") (name "Net-(U29-DI)") (class "Default")
      (node (ref "U29") (pin "4") (pinfunction "DI_4") (pintype "input"))
      (node (ref "U30") (pin "2") (pinfunction "Voa_2") (pintype "output"))
    )
    (net (code "97") (name "Net-(U29-RO)") (class "Default")
      (node (ref "U29") (pin "1") (pinfunction "RO_1") (pintype "output"))
      (node (ref "U30") (pin "3") (pinfunction "Vib_3") (pintype "input"))
    )
    (net (code "98") (name "Net-(U31-Vib)") (class "Default")
      (node (ref "U31") (pin "3") (pinfunction "Vib_3") (pintype "input"))
      (node (ref "U32") (pin "2") (pinfunction "R_2") (pintype "output"))
    )
    (net (code "99") (name "Net-(U31-Voa)") (class "Default")
      (node (ref "U31") (pin "2") (pinfunction "Voa_2") (pintype "output"))
      (node (ref "U32") (pin "3") (pinfunction "D_3") (pintype "input"))
    )
    (net (code "100") (name "unconnected-(P1-Pad8)") (class "Default")
      (node (ref "P1") (pin "8") (pinfunction "8_8") (pintype "passive"))
    )
    (net (code "101") (name "unconnected-(P1-Pad10)") (class "Default")
      (node (ref "P1") (pin "10") (pinfunction "10_10") (pintype "passive"))
    )
    (net (code "102") (name "unconnected-(P3-Pad3)") (class "Default")
      (node (ref "P3") (pin "3") (pinfunction "3_3") (pintype "passive"))
    )
    (net (code "103") (name "unconnected-(P3-Pad4)") (class "Default")
      (node (ref "P3") (pin "4") (pinfunction "4_4") (pintype "passive"))
    )
    (net (code "104") (name "unconnected-(P3-Pad7)") (class "Default")
      (node (ref "P3") (pin "7") (pinfunction "7_7") (pintype "passive"))
    )
    (net (code "105") (name "unconnected-(P3-Pad8)") (class "Default")
      (node (ref "P3") (pin "8") (pinfunction "8_8") (pintype "passive"))
    )
    (net (code "106") (name "unconnected-(P3-Pad9)") (class "Default")
      (node (ref "P3") (pin "9") (pinfunction "9_9") (pintype "passive"))
    )
    (net (code "107") (name "unconnected-(P3-Pad10)") (class "Default")
      (node (ref "P3") (pin "10") (pinfunction "10_10") (pintype "passive"))
    )
    (net (code "108") (name "unconnected-(U16A-PA1-Pad15)") (class "Default")
      (node (ref "U16") (pin "15") (pinfunction "PA1_15") (pintype "bidirectional"))
    )
    (net (code "109") (name "unconnected-(U16A-PA8-Pad41)") (class "Default")
      (node (ref "U16") (pin "41") (pinfunction "PA8_41") (pintype "bidirectional"))
    )
    (net (code "110") (name "unconnected-(U16A-PA11-Pad44)") (class "Default")
      (node (ref "U16") (pin "44") (pinfunction "PA11_44") (pintype "bidirectional"))
    )
    (net (code "111") (name "unconnected-(U16A-PC13-Pad2)") (class "Default")
      (node (ref "U16") (pin "2") (pinfunction "PC13_2") (pintype "bidirectional"))
    )
    (net (code "112") (name "unconnected-(U16A-PC14-OSC32_IN(PC14)-Pad3)") (class "Default")
      (node (ref "U16") (pin "3") (pinfunction "PC14-OSC32_IN(PC14)_3") (pintype "bidirectional"))
    )
    (net (code "113") (name "unconnected-(U16A-PC15-OSC32_OUT(PC15)-Pad4)") (class "Default")
      (node (ref "U16") (pin "4") (pinfunction "PC15-OSC32_OUT(PC15)_4") (pintype "bidirectional"))
    )
    (net (code "114") (name "unconnected-(U16A-PF4-Pad18)") (class "Default")
      (node (ref "U16") (pin "18") (pinfunction "PF4_18") (pintype "bidirectional"))
    )
    (net (code "115") (name "unconnected-(U28-NC-Pad1)") (class "Default")
      (node (ref "U28") (pin "1") (pinfunction "NC_1") (pintype "passive"))
    )
    (net (code "116") (name "unconnected-(U28-NC-Pad4)") (class "Default")
      (node (ref "U28") (pin "4") (pinfunction "NC_4") (pintype "passive"))
    )
  )
)
